# Sheet1.net
KiCad netlist of a schematic drawn in Altium Designer
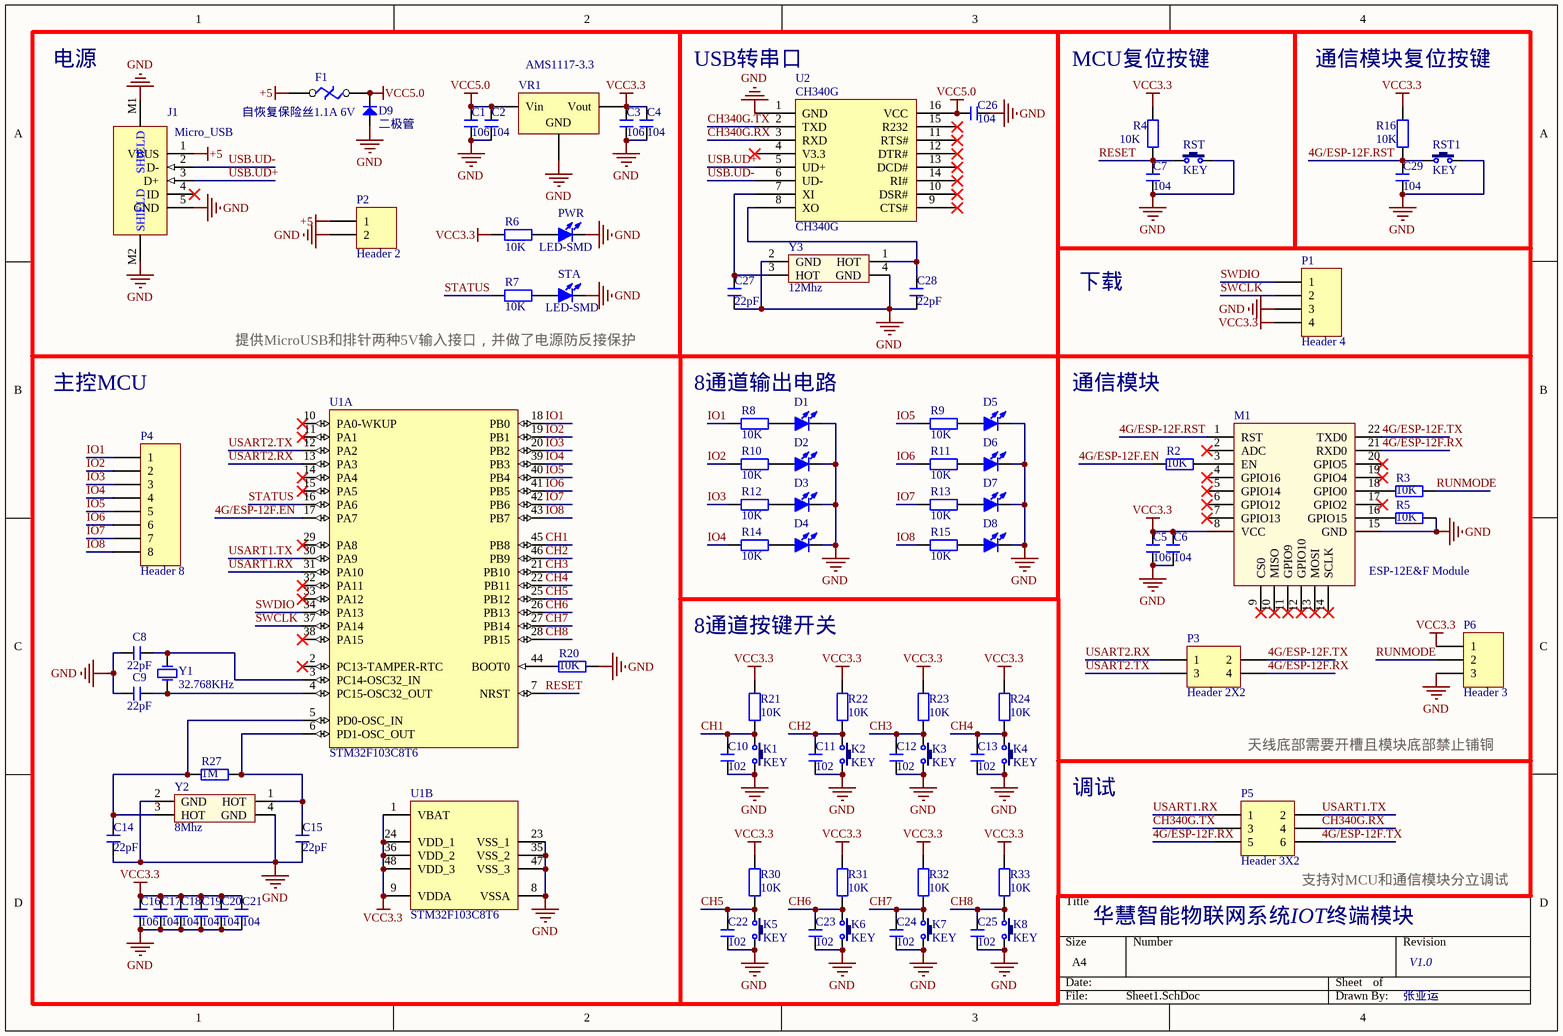
[diagram p0: Sheet1.SchDoc]

(export (version "E")
  (design (tool "Eeschema 10.0.6"))
  (components
    (comp (ref "C1")
      (value "106")
      (footprint "LC-0603_C")
      (description "无极性贴片电容")
      (fields (field (name "版权归属") "源创客"))
      (libsource (lib "MySchlib") (part "C"))
    )
    (comp (ref "C2")
      (value "104")
      (footprint "LC-0603_C")
      (description "无极性贴片电容")
      (fields (field (name "版权归属") "源创客"))
      (libsource (lib "MySchlib") (part "C"))
    )
    (comp (ref "C3")
      (value "106")
      (footprint "LC-0603_C")
      (description "无极性贴片电容")
      (fields (field (name "版权归属") "源创客"))
      (libsource (lib "MySchlib") (part "C"))
    )
    (comp (ref "C4")
      (value "104")
      (footprint "LC-0603_C")
      (description "无极性贴片电容")
      (fields (field (name "版权归属") "源创客"))
      (libsource (lib "MySchlib") (part "C"))
    )
    (comp (ref "C5")
      (value "106")
      (footprint "LC-0603_C")
      (description "无极性贴片电容")
      (fields (field (name "版权归属") "源创客"))
      (libsource (lib "MySchlib") (part "C"))
    )
    (comp (ref "C6")
      (value "104")
      (footprint "LC-0603_C")
      (description "无极性贴片电容")
      (fields (field (name "版权归属") "源创客"))
      (libsource (lib "MySchlib") (part "C"))
    )
    (comp (ref "C7")
      (value "104")
      (footprint "LC-0603_C")
      (description "无极性贴片电容")
      (fields (field (name "版权归属") "源创客"))
      (libsource (lib "MySchlib") (part "C"))
    )
    (comp (ref "C8")
      (value "22pF")
      (footprint "LC-0603_C")
      (description "无极性贴片电容")
      (fields (field (name "版权归属") "源创客"))
      (libsource (lib "MySchlib") (part "C"))
    )
    (comp (ref "C9")
      (value "22pF")
      (footprint "LC-0603_C")
      (description "无极性贴片电容")
      (fields (field (name "版权归属") "源创客"))
      (libsource (lib "MySchlib") (part "C"))
    )
    (comp (ref "C10")
      (value "102")
      (footprint "LC-0603_C")
      (description "无极性贴片电容")
      (fields (field (name "版权归属") "源创客"))
      (libsource (lib "MySchlib") (part "C"))
    )
    (comp (ref "C11")
      (value "102")
      (footprint "LC-0603_C")
      (description "无极性贴片电容")
      (fields (field (name "版权归属") "源创客"))
      (libsource (lib "MySchlib") (part "C"))
    )
    (comp (ref "C12")
      (value "102")
      (footprint "LC-0603_C")
      (description "无极性贴片电容")
      (fields (field (name "版权归属") "源创客"))
      (libsource (lib "MySchlib") (part "C"))
    )
    (comp (ref "C13")
      (value "102")
      (footprint "LC-0603_C")
      (description "无极性贴片电容")
      (fields (field (name "版权归属") "源创客"))
      (libsource (lib "MySchlib") (part "C"))
    )
    (comp (ref "C14")
      (value "22pF")
      (footprint "LC-0603_C")
      (description "无极性贴片电容")
      (fields (field (name "版权归属") "源创客"))
      (libsource (lib "MySchlib") (part "C"))
    )
    (comp (ref "C15")
      (value "22pF")
      (footprint "LC-0603_C")
      (description "无极性贴片电容")
      (fields (field (name "版权归属") "源创客"))
      (libsource (lib "MySchlib") (part "C"))
    )
    (comp (ref "C16")
      (value "106")
      (footprint "LC-0603_C")
      (description "无极性贴片电容")
      (fields (field (name "版权归属") "源创客"))
      (libsource (lib "MySchlib") (part "C"))
    )
    (comp (ref "C17")
      (value "104")
      (footprint "LC-0603_C")
      (description "无极性贴片电容")
      (fields (field (name "版权归属") "源创客"))
      (libsource (lib "MySchlib") (part "C"))
    )
    (comp (ref "C18")
      (value "104")
      (footprint "LC-0603_C")
      (description "无极性贴片电容")
      (fields (field (name "版权归属") "源创客"))
      (libsource (lib "MySchlib") (part "C"))
    )
    (comp (ref "C19")
      (value "104")
      (footprint "LC-0603_C")
      (description "无极性贴片电容")
      (fields (field (name "版权归属") "源创客"))
      (libsource (lib "MySchlib") (part "C"))
    )
    (comp (ref "C20")
      (value "104")
      (footprint "LC-0603_C")
      (description "无极性贴片电容")
      (fields (field (name "版权归属") "源创客"))
      (libsource (lib "MySchlib") (part "C"))
    )
    (comp (ref "C21")
      (value "104")
      (footprint "LC-0603_C")
      (description "无极性贴片电容")
      (fields (field (name "版权归属") "源创客"))
      (libsource (lib "MySchlib") (part "C"))
    )
    (comp (ref "C22")
      (value "102")
      (footprint "LC-0603_C")
      (description "无极性贴片电容")
      (fields (field (name "版权归属") "源创客"))
      (libsource (lib "MySchlib") (part "C"))
    )
    (comp (ref "C23")
      (value "102")
      (footprint "LC-0603_C")
      (description "无极性贴片电容")
      (fields (field (name "版权归属") "源创客"))
      (libsource (lib "MySchlib") (part "C"))
    )
    (comp (ref "C24")
      (value "102")
      (footprint "LC-0603_C")
      (description "无极性贴片电容")
      (fields (field (name "版权归属") "源创客"))
      (libsource (lib "MySchlib") (part "C"))
    )
    (comp (ref "C25")
      (value "102")
      (footprint "LC-0603_C")
      (description "无极性贴片电容")
      (fields (field (name "版权归属") "源创客"))
      (libsource (lib "MySchlib") (part "C"))
    )
    (comp (ref "C26")
      (value "104")
      (footprint "LC-0603_C")
      (description "无极性贴片电容")
      (fields (field (name "版权归属") "源创客"))
      (libsource (lib "MySchlib") (part "C"))
    )
    (comp (ref "C27")
      (value "22pF")
      (footprint "LC-0603_C")
      (description "无极性贴片电容")
      (fields (field (name "版权归属") "源创客"))
      (libsource (lib "MySchlib") (part "C"))
    )
    (comp (ref "C28")
      (value "22pF")
      (footprint "LC-0603_C")
      (description "无极性贴片电容")
      (fields (field (name "版权归属") "源创客"))
      (libsource (lib "MySchlib") (part "C"))
    )
    (comp (ref "C29")
      (value "104")
      (footprint "LC-0603_C")
      (description "无极性贴片电容")
      (fields (field (name "版权归属") "源创客"))
      (libsource (lib "MySchlib") (part "C"))
    )
    (comp (ref "D1")
      (value "LED-SMD")
      (footprint "LC-0603_LED_S1")
      (description "贴片LED")
      (fields (field (name "版权归属") "源创客"))
      (libsource (lib "MySchlib") (part "LED-SMD"))
    )
    (comp (ref "D2")
      (value "LED-SMD")
      (footprint "LC-0603_LED_S1")
      (description "贴片LED")
      (fields (field (name "版权归属") "源创客"))
      (libsource (lib "MySchlib") (part "LED-SMD"))
    )
    (comp (ref "D3")
      (value "LED-SMD")
      (footprint "LC-0603_LED_S1")
      (description "贴片LED")
      (fields (field (name "版权归属") "源创客"))
      (libsource (lib "MySchlib") (part "LED-SMD"))
    )
    (comp (ref "D4")
      (value "LED-SMD")
      (footprint "LC-0603_LED_S1")
      (description "贴片LED")
      (fields (field (name "版权归属") "源创客"))
      (libsource (lib "MySchlib") (part "LED-SMD"))
    )
    (comp (ref "D5")
      (value "LED-SMD")
      (footprint "LC-0603_LED_S1")
      (description "贴片LED")
      (fields (field (name "版权归属") "源创客"))
      (libsource (lib "MySchlib") (part "LED-SMD"))
    )
    (comp (ref "D6")
      (value "LED-SMD")
      (footprint "LC-0603_LED_S1")
      (description "贴片LED")
      (fields (field (name "版权归属") "源创客"))
      (libsource (lib "MySchlib") (part "LED-SMD"))
    )
    (comp (ref "D7")
      (value "LED-SMD")
      (footprint "LC-0603_LED_S1")
      (description "贴片LED")
      (fields (field (name "版权归属") "源创客"))
      (libsource (lib "MySchlib") (part "LED-SMD"))
    )
    (comp (ref "D8")
      (value "LED-SMD")
      (footprint "LC-0603_LED_S1")
      (description "贴片LED")
      (fields (field (name "版权归属") "源创客"))
      (libsource (lib "MySchlib") (part "LED-SMD"))
    )
    (comp (ref "D9")
      (value "二极管")
      (footprint "LC-SOD-323")
      (description "普通二极管")
      (libsource (lib "MySchlib") (part "二极管"))
    )
    (comp (ref "F1")
      (value "自恢复保险丝1.1A 6V")
      (footprint "LC-1206_R")
      (description "1206 贴片自恢复保险丝/保险管 PPTC MF-NSMF110-2 1.1A 6V")
      (libsource (lib "MySchlib") (part "F"))
    )
    (comp (ref "J1")
      (value "Micro_USB")
      (footprint "USB-MICRO_B")
      (description "Micro_usb")
      (libsource (lib "MySchlib") (part "Micro_USB"))
    )
    (comp (ref "K1")
      (value "KEY")
      (footprint "SWT3*4")
      (description "按键")
      (fields (field (name "版权归属") "源创客"))
      (libsource (lib "MySchlib") (part "KEY"))
    )
    (comp (ref "K2")
      (value "KEY")
      (footprint "SWT3*4")
      (description "按键")
      (fields (field (name "版权归属") "源创客"))
      (libsource (lib "MySchlib") (part "KEY"))
    )
    (comp (ref "K3")
      (value "KEY")
      (footprint "SWT3*4")
      (description "按键")
      (fields (field (name "版权归属") "源创客"))
      (libsource (lib "MySchlib") (part "KEY"))
    )
    (comp (ref "K4")
      (value "KEY")
      (footprint "SWT3*4")
      (description "按键")
      (fields (field (name "版权归属") "源创客"))
      (libsource (lib "MySchlib") (part "KEY"))
    )
    (comp (ref "K5")
      (value "KEY")
      (footprint "SWT3*4")
      (description "按键")
      (fields (field (name "版权归属") "源创客"))
      (libsource (lib "MySchlib") (part "KEY"))
    )
    (comp (ref "K6")
      (value "KEY")
      (footprint "SWT3*4")
      (description "按键")
      (fields (field (name "版权归属") "源创客"))
      (libsource (lib "MySchlib") (part "KEY"))
    )
    (comp (ref "K7")
      (value "KEY")
      (footprint "SWT3*4")
      (description "按键")
      (fields (field (name "版权归属") "源创客"))
      (libsource (lib "MySchlib") (part "KEY"))
    )
    (comp (ref "K8")
      (value "KEY")
      (footprint "SWT3*4")
      (description "按键")
      (fields (field (name "版权归属") "源创客"))
      (libsource (lib "MySchlib") (part "KEY"))
    )
    (comp (ref "M1")
      (value "ESP-12E&F Module")
      (footprint "ESP-12E&F Module")
      (libsource (lib "MySchlib") (part "ESP-12E&F Module"))
    )
    (comp (ref "P1")
      (value "Header 4")
      (footprint "HDR1X4")
      (description "Header, 4-Pin")
      (fields (field (name "PUBLISHER") "Altium Limited"))
      (libsource (lib "Miscellaneous Connectors") (part "Header 4"))
    )
    (comp (ref "P2")
      (value "Header 2")
      (footprint "HDR1X2")
      (description "Header, 2-Pin")
      (fields (field (name "PUBLISHER") "Altium Limited"))
      (libsource (lib "Miscellaneous Connectors") (part "Header 2"))
    )
    (comp (ref "P3")
      (value "Header 2X2")
      (footprint "HDR2X2")
      (description "Header, 2-Pin, Dual row")
      (fields (field (name "PUBLISHER") "Altium Limited"))
      (libsource (lib "Miscellaneous Connectors") (part "Header 2X2"))
    )
    (comp (ref "P4")
      (value "Header 8")
      (footprint "HDR1X8")
      (description "Header, 8-Pin")
      (fields (field (name "PUBLISHER") "Altium Limited"))
      (libsource (lib "Miscellaneous Connectors") (part "Header 8"))
    )
    (comp (ref "P5")
      (value "Header 3X2")
      (footprint "HDR2X3")
      (description "Header, 3-Pin, Dual row")
      (fields (field (name "PUBLISHER") "Altium Limited"))
      (libsource (lib "Miscellaneous Connectors") (part "Header 3X2"))
    )
    (comp (ref "P6")
      (value "Header 3")
      (footprint "HDR1X3")
      (description "Header, 3-Pin")
      (fields (field (name "PUBLISHER") "Altium Limited"))
      (libsource (lib "Miscellaneous Connectors") (part "Header 3"))
    )
    (comp (ref "PWR")
      (value "LED-SMD")
      (footprint "LC-0603_LED_S1")
      (description "贴片LED")
      (fields (field (name "版权归属") "源创客"))
      (libsource (lib "MySchlib") (part "LED-SMD"))
    )
    (comp (ref "R2")
      (value "10K")
      (footprint "LC-0603_R")
      (description "电阻")
      (libsource (lib "") (part "R_2"))
    )
    (comp (ref "R3")
      (value "10K")
      (footprint "LC-0603_R")
      (description "电阻")
      (libsource (lib "") (part "R_2"))
    )
    (comp (ref "R4")
      (value "10K")
      (footprint "LC-0603_R")
      (description "电阻")
      (libsource (lib "MySchlib") (part "R"))
    )
    (comp (ref "R5")
      (value "10K")
      (footprint "LC-0603_R")
      (description "电阻")
      (libsource (lib "") (part "R_2"))
    )
    (comp (ref "R6")
      (value "10K")
      (footprint "LC-0603_R")
      (description "电阻")
      (libsource (lib "") (part "R_3"))
    )
    (comp (ref "R7")
      (value "10K")
      (footprint "LC-0603_R")
      (description "电阻")
      (libsource (lib "") (part "R_3"))
    )
    (comp (ref "R8")
      (value "10K")
      (footprint "LC-0603_R")
      (description "电阻")
      (libsource (lib "") (part "R_3"))
    )
    (comp (ref "R9")
      (value "10K")
      (footprint "LC-0603_R")
      (description "电阻")
      (libsource (lib "") (part "R_3"))
    )
    (comp (ref "R10")
      (value "10K")
      (footprint "LC-0603_R")
      (description "电阻")
      (libsource (lib "") (part "R_3"))
    )
    (comp (ref "R11")
      (value "10K")
      (footprint "LC-0603_R")
      (description "电阻")
      (libsource (lib "") (part "R_3"))
    )
    (comp (ref "R12")
      (value "10K")
      (footprint "LC-0603_R")
      (description "电阻")
      (libsource (lib "") (part "R_3"))
    )
    (comp (ref "R13")
      (value "10K")
      (footprint "LC-0603_R")
      (description "电阻")
      (libsource (lib "") (part "R_3"))
    )
    (comp (ref "R14")
      (value "10K")
      (footprint "LC-0603_R")
      (description "电阻")
      (libsource (lib "") (part "R_3"))
    )
    (comp (ref "R15")
      (value "10K")
      (footprint "LC-0603_R")
      (description "电阻")
      (libsource (lib "") (part "R_3"))
    )
    (comp (ref "R16")
      (value "10K")
      (footprint "LC-0603_R")
      (description "电阻")
      (libsource (lib "MySchlib") (part "R"))
    )
    (comp (ref "R20")
      (value "10K")
      (footprint "LC-0603_R")
      (description "电阻")
      (libsource (lib "") (part "R_2"))
    )
    (comp (ref "R21")
      (value "10K")
      (footprint "LC-0603_R")
      (description "电阻")
      (libsource (lib "") (part "R_1"))
    )
    (comp (ref "R22")
      (value "10K")
      (footprint "LC-0603_R")
      (description "电阻")
      (libsource (lib "") (part "R_1"))
    )
    (comp (ref "R23")
      (value "10K")
      (footprint "LC-0603_R")
      (description "电阻")
      (libsource (lib "") (part "R_1"))
    )
    (comp (ref "R24")
      (value "10K")
      (footprint "LC-0603_R")
      (description "电阻")
      (libsource (lib "") (part "R_1"))
    )
    (comp (ref "R27")
      (value "1M")
      (footprint "LC-0603_R")
      (description "电阻")
      (libsource (lib "") (part "R_2"))
    )
    (comp (ref "R30")
      (value "10K")
      (footprint "LC-0603_R")
      (description "电阻")
      (libsource (lib "") (part "R_1"))
    )
    (comp (ref "R31")
      (value "10K")
      (footprint "LC-0603_R")
      (description "电阻")
      (libsource (lib "") (part "R_1"))
    )
    (comp (ref "R32")
      (value "10K")
      (footprint "LC-0603_R")
      (description "电阻")
      (libsource (lib "") (part "R_1"))
    )
    (comp (ref "R33")
      (value "10K")
      (footprint "LC-0603_R")
      (description "电阻")
      (libsource (lib "") (part "R_1"))
    )
    (comp (ref "RST")
      (value "KEY")
      (footprint "SWT3*4")
      (description "按键")
      (fields (field (name "版权归属") "源创客"))
      (libsource (lib "") (part "KEY_1"))
    )
    (comp (ref "RST1")
      (value "KEY")
      (footprint "SWT3*4")
      (description "按键")
      (fields (field (name "版权归属") "源创客"))
      (libsource (lib "") (part "KEY_1"))
    )
    (comp (ref "STA")
      (value "LED-SMD")
      (footprint "LC-0603_LED_S1")
      (description "贴片LED")
      (fields (field (name "版权归属") "源创客"))
      (libsource (lib "MySchlib") (part "LED-SMD"))
    )
    (comp (ref "U1")
      (value "STM32F103C8T6")
      (footprint "STM-LQFP48_L")
      (libsource (lib "STMicroelectronics STM32 F1") (part "STM32F103C8T6"))
    )
    (comp (ref "U2")
      (value "CH340G")
      (footprint "SOIC-16_150mil")
      (description "USB")
      (libsource (lib "02 Miscellaneous_Devices_ZSF_Library") (part "CH340G"))
    )
    (comp (ref "VR1")
      (value "AMS1117-3.3")
      (footprint "LC-SOT-223")
      (description "低压差线性稳压(LDO)")
      (libsource (lib "MySchlib") (part "SOT-223 AMS1117-3.3"))
    )
    (comp (ref "Y1")
      (value "32.768KHz")
      (footprint "LC-SMD-3215_2P FC - 135")
      (description "普通晶振")
      (fields (field (name "PUBLISHER") "Altium Limited"))
      (libsource (lib "MySchlib") (part "XTAL"))
    )
    (comp (ref "Y2")
      (value "8Mhz")
      (footprint "LC-SMD-3225_4P")
      (description "3225贴片无源晶振")
      (libsource (lib "MySchlib") (part "XTAL_3225"))
    )
    (comp (ref "Y3")
      (value "12Mhz")
      (footprint "LC-SMD-3225_4P")
      (description "3225贴片无源晶振")
      (libsource (lib "MySchlib") (part "XTAL_3225"))
    )
  )
  (nets
    (net (code "1") (name "+5") (class "Default")
      (node (ref "F1") (pin "1") (pinfunction "1_1") (pintype "passive"))
      (node (ref "J1") (pin "1") (pinfunction "VBUS_1") (pintype "power_in"))
      (node (ref "P2") (pin "1") (pinfunction "1_1") (pintype "passive"))
    )
    (net (code "2") (name "/4G{slash}ESP-12F.EN") (class "Default")
      (node (ref "R2") (pin "2") (pinfunction "2_2") (pintype "passive"))
      (node (ref "U1") (pin "17") (pinfunction "PA7_17") (pintype "bidirectional"))
    )
    (net (code "3") (name "/4G{slash}ESP-12F.RST") (class "Default")
      (node (ref "C29") (pin "2") (pinfunction "2_2") (pintype "passive"))
      (node (ref "M1") (pin "1") (pinfunction "RST_1") (pintype "passive"))
      (node (ref "R16") (pin "1") (pinfunction "1_1") (pintype "passive"))
      (node (ref "RST1") (pin "1") (pinfunction "1_1") (pintype "passive"))
    )
    (net (code "4") (name "/4G{slash}ESP-12F.RX") (class "Default")
      (node (ref "M1") (pin "21") (pinfunction "RXD0_21") (pintype "passive"))
      (node (ref "P3") (pin "4") (pinfunction "4_4") (pintype "passive"))
      (node (ref "P5") (pin "5") (pinfunction "5_5") (pintype "passive"))
    )
    (net (code "5") (name "/4G{slash}ESP-12F.TX") (class "Default")
      (node (ref "M1") (pin "22") (pinfunction "TXD0_22") (pintype "passive"))
      (node (ref "P3") (pin "2") (pinfunction "2_2") (pintype "passive"))
      (node (ref "P5") (pin "6") (pinfunction "6_6") (pintype "passive"))
    )
    (net (code "6") (name "/CH1") (class "Default")
      (node (ref "C10") (pin "1") (pinfunction "1_1") (pintype "passive"))
      (node (ref "K1") (pin "1") (pinfunction "1_1") (pintype "passive"))
      (node (ref "R21") (pin "2") (pinfunction "2_2") (pintype "passive"))
      (node (ref "U1") (pin "45") (pinfunction "PB8_45") (pintype "bidirectional"))
    )
    (net (code "7") (name "/CH2") (class "Default")
      (node (ref "C11") (pin "1") (pinfunction "1_1") (pintype "passive"))
      (node (ref "K2") (pin "1") (pinfunction "1_1") (pintype "passive"))
      (node (ref "R22") (pin "2") (pinfunction "2_2") (pintype "passive"))
      (node (ref "U1") (pin "46") (pinfunction "PB9_46") (pintype "bidirectional"))
    )
    (net (code "8") (name "/CH3") (class "Default")
      (node (ref "C12") (pin "1") (pinfunction "1_1") (pintype "passive"))
      (node (ref "K3") (pin "1") (pinfunction "1_1") (pintype "passive"))
      (node (ref "R23") (pin "2") (pinfunction "2_2") (pintype "passive"))
      (node (ref "U1") (pin "21") (pinfunction "PB10_21") (pintype "bidirectional"))
    )
    (net (code "9") (name "/CH4") (class "Default")
      (node (ref "C13") (pin "1") (pinfunction "1_1") (pintype "passive"))
      (node (ref "K4") (pin "1") (pinfunction "1_1") (pintype "passive"))
      (node (ref "R24") (pin "2") (pinfunction "2_2") (pintype "passive"))
      (node (ref "U1") (pin "22") (pinfunction "PB11_22") (pintype "bidirectional"))
    )
    (net (code "10") (name "/CH5") (class "Default")
      (node (ref "C22") (pin "1") (pinfunction "1_1") (pintype "passive"))
      (node (ref "K5") (pin "1") (pinfunction "1_1") (pintype "passive"))
      (node (ref "R30") (pin "2") (pinfunction "2_2") (pintype "passive"))
      (node (ref "U1") (pin "25") (pinfunction "PB12_25") (pintype "bidirectional"))
    )
    (net (code "11") (name "/CH6") (class "Default")
      (node (ref "C23") (pin "1") (pinfunction "1_1") (pintype "passive"))
      (node (ref "K6") (pin "1") (pinfunction "1_1") (pintype "passive"))
      (node (ref "R31") (pin "2") (pinfunction "2_2") (pintype "passive"))
      (node (ref "U1") (pin "26") (pinfunction "PB13_26") (pintype "bidirectional"))
    )
    (net (code "12") (name "/CH7") (class "Default")
      (node (ref "C24") (pin "1") (pinfunction "1_1") (pintype "passive"))
      (node (ref "K7") (pin "1") (pinfunction "1_1") (pintype "passive"))
      (node (ref "R32") (pin "2") (pinfunction "2_2") (pintype "passive"))
      (node (ref "U1") (pin "27") (pinfunction "PB14_27") (pintype "bidirectional"))
    )
    (net (code "13") (name "/CH8") (class "Default")
      (node (ref "C25") (pin "1") (pinfunction "1_1") (pintype "passive"))
      (node (ref "K8") (pin "1") (pinfunction "1_1") (pintype "passive"))
      (node (ref "R33") (pin "2") (pinfunction "2_2") (pintype "passive"))
      (node (ref "U1") (pin "28") (pinfunction "PB15_28") (pintype "bidirectional"))
    )
    (net (code "14") (name "/CH340G.RX") (class "Default")
      (node (ref "P5") (pin "4") (pinfunction "4_4") (pintype "passive"))
      (node (ref "U2") (pin "3") (pinfunction "RXD_3") (pintype "passive"))
    )
    (net (code "15") (name "/CH340G.TX") (class "Default")
      (node (ref "P5") (pin "3") (pinfunction "3_3") (pintype "passive"))
      (node (ref "U2") (pin "2") (pinfunction "TXD_2") (pintype "passive"))
    )
    (net (code "16") (name "/IO1") (class "Default")
      (node (ref "P4") (pin "1") (pinfunction "1_1") (pintype "passive"))
      (node (ref "R8") (pin "1") (pinfunction "1_1") (pintype "passive"))
      (node (ref "U1") (pin "18") (pinfunction "PB0_18") (pintype "bidirectional"))
    )
    (net (code "17") (name "/IO2") (class "Default")
      (node (ref "P4") (pin "2") (pinfunction "2_2") (pintype "passive"))
      (node (ref "R10") (pin "1") (pinfunction "1_1") (pintype "passive"))
      (node (ref "U1") (pin "19") (pinfunction "PB1_19") (pintype "bidirectional"))
    )
    (net (code "18") (name "/IO3") (class "Default")
      (node (ref "P4") (pin "3") (pinfunction "3_3") (pintype "passive"))
      (node (ref "R12") (pin "1") (pinfunction "1_1") (pintype "passive"))
      (node (ref "U1") (pin "20") (pinfunction "PB2_20") (pintype "bidirectional"))
    )
    (net (code "19") (name "/IO4") (class "Default")
      (node (ref "P4") (pin "4") (pinfunction "4_4") (pintype "passive"))
      (node (ref "R14") (pin "1") (pinfunction "1_1") (pintype "passive"))
      (node (ref "U1") (pin "39") (pinfunction "PB3_39") (pintype "bidirectional"))
    )
    (net (code "20") (name "/IO5") (class "Default")
      (node (ref "P4") (pin "5") (pinfunction "5_5") (pintype "passive"))
      (node (ref "R9") (pin "1") (pinfunction "1_1") (pintype "passive"))
      (node (ref "U1") (pin "40") (pinfunction "PB4_40") (pintype "bidirectional"))
    )
    (net (code "21") (name "/IO6") (class "Default")
      (node (ref "P4") (pin "6") (pinfunction "6_6") (pintype "passive"))
      (node (ref "R11") (pin "1") (pinfunction "1_1") (pintype "passive"))
      (node (ref "U1") (pin "41") (pinfunction "PB5_41") (pintype "bidirectional"))
    )
    (net (code "22") (name "/IO7") (class "Default")
      (node (ref "P4") (pin "7") (pinfunction "7_7") (pintype "passive"))
      (node (ref "R13") (pin "1") (pinfunction "1_1") (pintype "passive"))
      (node (ref "U1") (pin "42") (pinfunction "PB6_42") (pintype "bidirectional"))
    )
    (net (code "23") (name "/IO8") (class "Default")
      (node (ref "P4") (pin "8") (pinfunction "8_8") (pintype "passive"))
      (node (ref "R15") (pin "1") (pinfunction "1_1") (pintype "passive"))
      (node (ref "U1") (pin "43") (pinfunction "PB7_43") (pintype "bidirectional"))
    )
    (net (code "24") (name "/RESET") (class "Default")
      (node (ref "C7") (pin "2") (pinfunction "2_2") (pintype "passive"))
      (node (ref "R4") (pin "1") (pinfunction "1_1") (pintype "passive"))
      (node (ref "RST") (pin "1") (pinfunction "1_1") (pintype "passive"))
      (node (ref "U1") (pin "7") (pinfunction "NRST_7") (pintype "bidirectional"))
    )
    (net (code "25") (name "/RUNMODE") (class "Default")
      (node (ref "P6") (pin "2") (pinfunction "2_2") (pintype "passive"))
      (node (ref "R3") (pin "1") (pinfunction "1_1") (pintype "passive"))
    )
    (net (code "26") (name "/STATUS") (class "Default")
      (node (ref "R7") (pin "1") (pinfunction "1_1") (pintype "passive"))
      (node (ref "U1") (pin "16") (pinfunction "PA6_16") (pintype "bidirectional"))
    )
    (net (code "27") (name "/SWCLK") (class "Default")
      (node (ref "P1") (pin "2") (pinfunction "2_2") (pintype "passive"))
      (node (ref "U1") (pin "37") (pinfunction "PA14_37") (pintype "bidirectional"))
    )
    (net (code "28") (name "/SWDIO") (class "Default")
      (node (ref "P1") (pin "1") (pinfunction "1_1") (pintype "passive"))
      (node (ref "U1") (pin "34") (pinfunction "PA13_34") (pintype "bidirectional"))
    )
    (net (code "29") (name "/USART1.RX") (class "Default")
      (node (ref "P5") (pin "1") (pinfunction "1_1") (pintype "passive"))
      (node (ref "U1") (pin "31") (pinfunction "PA10_31") (pintype "bidirectional"))
    )
    (net (code "30") (name "/USART1.TX") (class "Default")
      (node (ref "P5") (pin "2") (pinfunction "2_2") (pintype "passive"))
      (node (ref "U1") (pin "30") (pinfunction "PA9_30") (pintype "bidirectional"))
    )
    (net (code "31") (name "/USART2.RX") (class "Default")
      (node (ref "P3") (pin "1") (pinfunction "1_1") (pintype "passive"))
      (node (ref "U1") (pin "13") (pinfunction "PA3_13") (pintype "bidirectional"))
    )
    (net (code "32") (name "/USART2.TX") (class "Default")
      (node (ref "P3") (pin "3") (pinfunction "3_3") (pintype "passive"))
      (node (ref "U1") (pin "12") (pinfunction "PA2_12") (pintype "bidirectional"))
    )
    (net (code "33") (name "/USB.UD+") (class "Default")
      (node (ref "J1") (pin "3") (pinfunction "D+_3") (pintype "input"))
      (node (ref "U2") (pin "5") (pinfunction "UD+_5") (pintype "passive"))
    )
    (net (code "34") (name "/USB.UD-") (class "Default")
      (node (ref "J1") (pin "2") (pinfunction "D-_2") (pintype "input"))
      (node (ref "U2") (pin "6") (pinfunction "UD-_6") (pintype "passive"))
    )
    (net (code "35") (name "GND") (class "Default")
      (node (ref "C1") (pin "2") (pinfunction "2_2") (pintype "passive"))
      (node (ref "C10") (pin "2") (pinfunction "2_2") (pintype "passive"))
      (node (ref "C11") (pin "2") (pinfunction "2_2") (pintype "passive"))
      (node (ref "C12") (pin "2") (pinfunction "2_2") (pintype "passive"))
      (node (ref "C13") (pin "2") (pinfunction "2_2") (pintype "passive"))
      (node (ref "C14") (pin "2") (pinfunction "2_2") (pintype "passive"))
      (node (ref "C15") (pin "2") (pinfunction "2_2") (pintype "passive"))
      (node (ref "C16") (pin "2") (pinfunction "2_2") (pintype "passive"))
      (node (ref "C17") (pin "2") (pinfunction "2_2") (pintype "passive"))
      (node (ref "C18") (pin "2") (pinfunction "2_2") (pintype "passive"))
      (node (ref "C19") (pin "2") (pinfunction "2_2") (pintype "passive"))
      (node (ref "C2") (pin "2") (pinfunction "2_2") (pintype "passive"))
      (node (ref "C20") (pin "2") (pinfunction "2_2") (pintype "passive"))
      (node (ref "C21") (pin "2") (pinfunction "2_2") (pintype "passive"))
      (node (ref "C22") (pin "2") (pinfunction "2_2") (pintype "passive"))
      (node (ref "C23") (pin "2") (pinfunction "2_2") (pintype "passive"))
      (node (ref "C24") (pin "2") (pinfunction "2_2") (pintype "passive"))
      (node (ref "C25") (pin "2") (pinfunction "2_2") (pintype "passive"))
      (node (ref "C26") (pin "1") (pinfunction "1_1") (pintype "passive"))
      (node (ref "C27") (pin "2") (pinfunction "2_2") (pintype "passive"))
      (node (ref "C28") (pin "2") (pinfunction "2_2") (pintype "passive"))
      (node (ref "C29") (pin "1") (pinfunction "1_1") (pintype "passive"))
      (node (ref "C3") (pin "2") (pinfunction "2_2") (pintype "passive"))
      (node (ref "C4") (pin "2") (pinfunction "2_2") (pintype "passive"))
      (node (ref "C5") (pin "2") (pinfunction "2_2") (pintype "passive"))
      (node (ref "C6") (pin "2") (pinfunction "2_2") (pintype "passive"))
      (node (ref "C7") (pin "1") (pinfunction "1_1") (pintype "passive"))
      (node (ref "C8") (pin "1") (pinfunction "1_1") (pintype "passive"))
      (node (ref "C9") (pin "1") (pinfunction "1_1") (pintype "passive"))
      (node (ref "D1") (pin "2") (pinfunction "K_2") (pintype "passive"))
      (node (ref "D2") (pin "2") (pinfunction "K_2") (pintype "passive"))
      (node (ref "D3") (pin "2") (pinfunction "K_2") (pintype "passive"))
      (node (ref "D4") (pin "2") (pinfunction "K_2") (pintype "passive"))
      (node (ref "D5") (pin "2") (pinfunction "K_2") (pintype "passive"))
      (node (ref "D6") (pin "2") (pinfunction "K_2") (pintype "passive"))
      (node (ref "D7") (pin "2") (pinfunction "K_2") (pintype "passive"))
      (node (ref "D8") (pin "2") (pinfunction "K_2") (pintype "passive"))
      (node (ref "D9") (pin "1") (pintype "passive"))
      (node (ref "J1") (pin "5") (pinfunction "GND_5") (pintype "power_in"))
      (node (ref "J1") (pin "M1") (pinfunction "SHIELD_M1") (pintype "passive"))
      (node (ref "J1") (pin "M2") (pinfunction "SHIELD_M2") (pintype "passive"))
      (node (ref "K1") (pin "2") (pinfunction "2_2") (pintype "passive"))
      (node (ref "K2") (pin "2") (pinfunction "2_2") (pintype "passive"))
      (node (ref "K3") (pin "2") (pinfunction "2_2") (pintype "passive"))
      (node (ref "K4") (pin "2") (pinfunction "2_2") (pintype "passive"))
      (node (ref "K5") (pin "2") (pinfunction "2_2") (pintype "passive"))
      (node (ref "K6") (pin "2") (pinfunction "2_2") (pintype "passive"))
      (node (ref "K7") (pin "2") (pinfunction "2_2") (pintype "passive"))
      (node (ref "K8") (pin "2") (pinfunction "2_2") (pintype "passive"))
      (node (ref "M1") (pin "15") (pinfunction "GND_15") (pintype "passive"))
      (node (ref "P1") (pin "3") (pinfunction "3_3") (pintype "passive"))
      (node (ref "P2") (pin "2") (pinfunction "2_2") (pintype "passive"))
      (node (ref "P6") (pin "3") (pinfunction "3_3") (pintype "passive"))
      (node (ref "PWR") (pin "2") (pinfunction "K_2") (pintype "passive"))
      (node (ref "R20") (pin "1") (pinfunction "1_1") (pintype "passive"))
      (node (ref "R5") (pin "1") (pinfunction "1_1") (pintype "passive"))
      (node (ref "RST") (pin "2") (pinfunction "2_2") (pintype "passive"))
      (node (ref "RST1") (pin "2") (pinfunction "2_2") (pintype "passive"))
      (node (ref "STA") (pin "2") (pinfunction "K_2") (pintype "passive"))
      (node (ref "U1") (pin "23") (pinfunction "VSS_1_23") (pintype "power_in"))
      (node (ref "U1") (pin "35") (pinfunction "VSS_2_35") (pintype "power_in"))
      (node (ref "U1") (pin "47") (pinfunction "VSS_3_47") (pintype "power_in"))
      (node (ref "U1") (pin "8") (pinfunction "VSSA_8") (pintype "power_in"))
      (node (ref "U2") (pin "1") (pinfunction "GND_1") (pintype "passive"))
      (node (ref "VR1") (pin "1") (pinfunction "GND_1") (pintype "passive"))
      (node (ref "Y2") (pin "2") (pinfunction "GND_2") (pintype "passive"))
      (node (ref "Y2") (pin "4") (pinfunction "GND_4") (pintype "passive"))
      (node (ref "Y3") (pin "2") (pinfunction "GND_2") (pintype "passive"))
      (node (ref "Y3") (pin "4") (pinfunction "GND_4") (pintype "passive"))
    )
    (net (code "36") (name "Net-(D1-A)") (class "Default")
      (node (ref "D1") (pin "1") (pinfunction "A_1") (pintype "passive"))
      (node (ref "R8") (pin "2") (pinfunction "2_2") (pintype "passive"))
    )
    (net (code "37") (name "Net-(D2-A)") (class "Default")
      (node (ref "D2") (pin "1") (pinfunction "A_1") (pintype "passive"))
      (node (ref "R10") (pin "2") (pinfunction "2_2") (pintype "passive"))
    )
    (net (code "38") (name "Net-(D3-A)") (class "Default")
      (node (ref "D3") (pin "1") (pinfunction "A_1") (pintype "passive"))
      (node (ref "R12") (pin "2") (pinfunction "2_2") (pintype "passive"))
    )
    (net (code "39") (name "Net-(D4-A)") (class "Default")
      (node (ref "D4") (pin "1") (pinfunction "A_1") (pintype "passive"))
      (node (ref "R14") (pin "2") (pinfunction "2_2") (pintype "passive"))
    )
    (net (code "40") (name "Net-(D5-A)") (class "Default")
      (node (ref "D5") (pin "1") (pinfunction "A_1") (pintype "passive"))
      (node (ref "R9") (pin "2") (pinfunction "2_2") (pintype "passive"))
    )
    (net (code "41") (name "Net-(D6-A)") (class "Default")
      (node (ref "D6") (pin "1") (pinfunction "A_1") (pintype "passive"))
      (node (ref "R11") (pin "2") (pinfunction "2_2") (pintype "passive"))
    )
    (net (code "42") (name "Net-(D7-A)") (class "Default")
      (node (ref "D7") (pin "1") (pinfunction "A_1") (pintype "passive"))
      (node (ref "R13") (pin "2") (pinfunction "2_2") (pintype "passive"))
    )
    (net (code "43") (name "Net-(D8-A)") (class "Default")
      (node (ref "D8") (pin "1") (pinfunction "A_1") (pintype "passive"))
      (node (ref "R15") (pin "2") (pinfunction "2_2") (pintype "passive"))
    )
    (net (code "44") (name "Net-(M1-EN)") (class "Default")
      (node (ref "M1") (pin "3") (pinfunction "EN_3") (pintype "passive"))
      (node (ref "R2") (pin "1") (pinfunction "1_1") (pintype "passive"))
    )
    (net (code "45") (name "Net-(M1-GPIO0)") (class "Default")
      (node (ref "M1") (pin "18") (pinfunction "GPIO0_18") (pintype "passive"))
      (node (ref "R3") (pin "2") (pinfunction "2_2") (pintype "passive"))
    )
    (net (code "46") (name "Net-(M1-GPIO15)") (class "Default")
      (node (ref "M1") (pin "16") (pinfunction "GPIO15_16") (pintype "passive"))
      (node (ref "R5") (pin "2") (pinfunction "2_2") (pintype "passive"))
    )
    (net (code "47") (name "Net-(PWR-A)") (class "Default")
      (node (ref "PWR") (pin "1") (pinfunction "A_1") (pintype "passive"))
      (node (ref "R6") (pin "2") (pinfunction "2_2") (pintype "passive"))
    )
    (net (code "48") (name "Net-(STA-A)") (class "Default")
      (node (ref "R7") (pin "2") (pinfunction "2_2") (pintype "passive"))
      (node (ref "STA") (pin "1") (pinfunction "A_1") (pintype "passive"))
    )
    (net (code "49") (name "Net-(U1A-BOOT0)") (class "Default")
      (node (ref "R20") (pin "2") (pinfunction "2_2") (pintype "passive"))
      (node (ref "U1") (pin "44") (pinfunction "BOOT0_44") (pintype "input"))
    )
    (net (code "50") (name "Net-(U1A-PC14-OSC32_IN)") (class "Default")
      (node (ref "C8") (pin "2") (pinfunction "2_2") (pintype "passive"))
      (node (ref "U1") (pin "3") (pinfunction "PC14-OSC32_IN_3") (pintype "bidirectional"))
      (node (ref "Y1") (pin "2") (pinfunction "OSC2_2") (pintype "passive"))
    )
    (net (code "51") (name "Net-(U1A-PC15-OSC32_OUT)") (class "Default")
      (node (ref "C9") (pin "2") (pinfunction "2_2") (pintype "passive"))
      (node (ref "U1") (pin "4") (pinfunction "PC15-OSC32_OUT_4") (pintype "bidirectional"))
      (node (ref "Y1") (pin "1") (pinfunction "OSC1_1") (pintype "passive"))
    )
    (net (code "52") (name "Net-(U1A-PD0-OSC_IN)") (class "Default")
      (node (ref "C14") (pin "1") (pinfunction "1_1") (pintype "passive"))
      (node (ref "R27") (pin "2") (pinfunction "2_2") (pintype "passive"))
      (node (ref "U1") (pin "5") (pinfunction "PD0-OSC_IN_5") (pintype "bidirectional"))
      (node (ref "Y2") (pin "3") (pinfunction "HOT_3") (pintype "passive"))
    )
    (net (code "53") (name "Net-(U1A-PD1-OSC_OUT)") (class "Default")
      (node (ref "C15") (pin "1") (pinfunction "1_1") (pintype "passive"))
      (node (ref "R27") (pin "1") (pinfunction "1_1") (pintype "passive"))
      (node (ref "U1") (pin "6") (pinfunction "PD1-OSC_OUT_6") (pintype "bidirectional"))
      (node (ref "Y2") (pin "1") (pinfunction "HOT_1") (pintype "passive"))
    )
    (net (code "54") (name "Net-(U2-XI)") (class "Default")
      (node (ref "C27") (pin "1") (pinfunction "1_1") (pintype "passive"))
      (node (ref "U2") (pin "7") (pinfunction "XI_7") (pintype "passive"))
      (node (ref "Y3") (pin "3") (pinfunction "HOT_3") (pintype "passive"))
    )
    (net (code "55") (name "Net-(U2-XO)") (class "Default")
      (node (ref "C28") (pin "1") (pinfunction "1_1") (pintype "passive"))
      (node (ref "U2") (pin "8") (pinfunction "XO_8") (pintype "passive"))
      (node (ref "Y3") (pin "1") (pinfunction "HOT_1") (pintype "passive"))
    )
    (net (code "56") (name "VCC3.3") (class "Default")
      (node (ref "C16") (pin "1") (pinfunction "1_1") (pintype "passive"))
      (node (ref "C17") (pin "1") (pinfunction "1_1") (pintype "passive"))
      (node (ref "C18") (pin "1") (pinfunction "1_1") (pintype "passive"))
      (node (ref "C19") (pin "1") (pinfunction "1_1") (pintype "passive"))
      (node (ref "C20") (pin "1") (pinfunction "1_1") (pintype "passive"))
      (node (ref "C21") (pin "1") (pinfunction "1_1") (pintype "passive"))
      (node (ref "C3") (pin "1") (pinfunction "1_1") (pintype "passive"))
      (node (ref "C4") (pin "1") (pinfunction "1_1") (pintype "passive"))
      (node (ref "C5") (pin "1") (pinfunction "1_1") (pintype "passive"))
      (node (ref "C6") (pin "1") (pinfunction "1_1") (pintype "passive"))
      (node (ref "M1") (pin "8") (pinfunction "VCC_8") (pintype "passive"))
      (node (ref "P1") (pin "4") (pinfunction "4_4") (pintype "passive"))
      (node (ref "P6") (pin "1") (pinfunction "1_1") (pintype "passive"))
      (node (ref "R16") (pin "2") (pinfunction "2_2") (pintype "passive"))
      (node (ref "R21") (pin "1") (pinfunction "1_1") (pintype "passive"))
      (node (ref "R22") (pin "1") (pinfunction "1_1") (pintype "passive"))
      (node (ref "R23") (pin "1") (pinfunction "1_1") (pintype "passive"))
      (node (ref "R24") (pin "1") (pinfunction "1_1") (pintype "passive"))
      (node (ref "R30") (pin "1") (pinfunction "1_1") (pintype "passive"))
      (node (ref "R31") (pin "1") (pinfunction "1_1") (pintype "passive"))
      (node (ref "R32") (pin "1") (pinfunction "1_1") (pintype "passive"))
      (node (ref "R33") (pin "1") (pinfunction "1_1") (pintype "passive"))
      (node (ref "R4") (pin "2") (pinfunction "2_2") (pintype "passive"))
      (node (ref "R6") (pin "1") (pinfunction "1_1") (pintype "passive"))
      (node (ref "U1") (pin "1") (pinfunction "VBAT_1") (pintype "power_in"))
      (node (ref "U1") (pin "24") (pinfunction "VDD_1_24") (pintype "power_in"))
      (node (ref "U1") (pin "36") (pinfunction "VDD_2_36") (pintype "power_in"))
      (node (ref "U1") (pin "48") (pinfunction "VDD_3_48") (pintype "power_in"))
      (node (ref "U1") (pin "9") (pinfunction "VDDA_9") (pintype "power_in"))
      (node (ref "VR1") (pin "2") (pinfunction "Vout_2") (pintype "passive"))
    )
    (net (code "57") (name "VCC5.0") (class "Default")
      (node (ref "C1") (pin "1") (pinfunction "1_1") (pintype "passive"))
      (node (ref "C2") (pin "1") (pinfunction "1_1") (pintype "passive"))
      (node (ref "C26") (pin "2") (pinfunction "2_2") (pintype "passive"))
      (node (ref "D9") (pin "2") (pintype "passive"))
      (node (ref "F1") (pin "2") (pinfunction "2_2") (pintype "passive"))
      (node (ref "U2") (pin "16") (pinfunction "VCC_16") (pintype "passive"))
      (node (ref "VR1") (pin "3") (pinfunction "Vin_3") (pintype "passive"))
    )
    (net (code "58") (name "unconnected-(J1-ID-Pad4)") (class "Default")
      (node (ref "J1") (pin "4") (pinfunction "ID_4") (pintype "passive+no_connect"))
    )
    (net (code "59") (name "unconnected-(M1-ADC-Pad2)") (class "Default")
      (node (ref "M1") (pin "2") (pinfunction "ADC_2") (pintype "passive+no_connect"))
    )
    (net (code "60") (name "unconnected-(M1-CS0-Pad9)") (class "Default")
      (node (ref "M1") (pin "9") (pinfunction "CS0_9") (pintype "passive+no_connect"))
    )
    (net (code "61") (name "unconnected-(M1-GPIO2-Pad17)") (class "Default")
      (node (ref "M1") (pin "17") (pinfunction "GPIO2_17") (pintype "passive+no_connect"))
    )
    (net (code "62") (name "unconnected-(M1-GPIO4-Pad19)") (class "Default")
      (node (ref "M1") (pin "19") (pinfunction "GPIO4_19") (pintype "passive+no_connect"))
    )
    (net (code "63") (name "unconnected-(M1-GPIO5-Pad20)") (class "Default")
      (node (ref "M1") (pin "20") (pinfunction "GPIO5_20") (pintype "passive+no_connect"))
    )
    (net (code "64") (name "unconnected-(M1-GPIO9-Pad11)") (class "Default")
      (node (ref "M1") (pin "11") (pinfunction "GPIO9_11") (pintype "passive+no_connect"))
    )
    (net (code "65") (name "unconnected-(M1-GPIO10-Pad12)") (class "Default")
      (node (ref "M1") (pin "12") (pinfunction "GPIO10_12") (pintype "passive+no_connect"))
    )
    (net (code "66") (name "unconnected-(M1-GPIO12-Pad6)") (class "Default")
      (node (ref "M1") (pin "6") (pinfunction "GPIO12_6") (pintype "passive+no_connect"))
    )
    (net (code "67") (name "unconnected-(M1-GPIO13-Pad7)") (class "Default")
      (node (ref "M1") (pin "7") (pinfunction "GPIO13_7") (pintype "passive+no_connect"))
    )
    (net (code "68") (name "unconnected-(M1-GPIO14-Pad5)") (class "Default")
      (node (ref "M1") (pin "5") (pinfunction "GPIO14_5") (pintype "passive+no_connect"))
    )
    (net (code "69") (name "unconnected-(M1-GPIO16-Pad4)") (class "Default")
      (node (ref "M1") (pin "4") (pinfunction "GPIO16_4") (pintype "passive+no_connect"))
    )
    (net (code "70") (name "unconnected-(M1-MISO-Pad10)") (class "Default")
      (node (ref "M1") (pin "10") (pinfunction "MISO_10") (pintype "passive+no_connect"))
    )
    (net (code "71") (name "unconnected-(M1-MOSI-Pad13)") (class "Default")
      (node (ref "M1") (pin "13") (pinfunction "MOSI_13") (pintype "passive+no_connect"))
    )
    (net (code "72") (name "unconnected-(M1-SCLK-Pad14)") (class "Default")
      (node (ref "M1") (pin "14") (pinfunction "SCLK_14") (pintype "passive+no_connect"))
    )
    (net (code "73") (name "unconnected-(U1A-PA0-WKUP-Pad10)") (class "Default")
      (node (ref "U1") (pin "10") (pinfunction "PA0-WKUP_10") (pintype "bidirectional+no_connect"))
    )
    (net (code "74") (name "unconnected-(U1A-PA1-Pad11)") (class "Default")
      (node (ref "U1") (pin "11") (pinfunction "PA1_11") (pintype "bidirectional+no_connect"))
    )
    (net (code "75") (name "unconnected-(U1A-PA4-Pad14)") (class "Default")
      (node (ref "U1") (pin "14") (pinfunction "PA4_14") (pintype "bidirectional+no_connect"))
    )
    (net (code "76") (name "unconnected-(U1A-PA5-Pad15)") (class "Default")
      (node (ref "U1") (pin "15") (pinfunction "PA5_15") (pintype "bidirectional+no_connect"))
    )
    (net (code "77") (name "unconnected-(U1A-PA8-Pad29)") (class "Default")
      (node (ref "U1") (pin "29") (pinfunction "PA8_29") (pintype "bidirectional+no_connect"))
    )
    (net (code "78") (name "unconnected-(U1A-PA11-Pad32)") (class "Default")
      (node (ref "U1") (pin "32") (pinfunction "PA11_32") (pintype "bidirectional+no_connect"))
    )
    (net (code "79") (name "unconnected-(U1A-PA12-Pad33)") (class "Default")
      (node (ref "U1") (pin "33") (pinfunction "PA12_33") (pintype "bidirectional+no_connect"))
    )
    (net (code "80") (name "unconnected-(U1A-PA15-Pad38)") (class "Default")
      (node (ref "U1") (pin "38") (pinfunction "PA15_38") (pintype "bidirectional+no_connect"))
    )
    (net (code "81") (name "unconnected-(U1A-PC13-TAMPER-RTC-Pad2)") (class "Default")
      (node (ref "U1") (pin "2") (pinfunction "PC13-TAMPER-RTC_2") (pintype "bidirectional+no_connect"))
    )
    (net (code "82") (name "unconnected-(U2-CTS#-Pad9)") (class "Default")
      (node (ref "U2") (pin "9") (pinfunction "CTS#_9") (pintype "passive+no_connect"))
    )
    (net (code "83") (name "unconnected-(U2-DCD#-Pad13)") (class "Default")
      (node (ref "U2") (pin "13") (pinfunction "DCD#_13") (pintype "passive+no_connect"))
    )
    (net (code "84") (name "unconnected-(U2-DSR#-Pad10)") (class "Default")
      (node (ref "U2") (pin "10") (pinfunction "DSR#_10") (pintype "passive+no_connect"))
    )
    (net (code "85") (name "unconnected-(U2-DTR#-Pad12)") (class "Default")
      (node (ref "U2") (pin "12") (pinfunction "DTR#_12") (pintype "passive+no_connect"))
    )
    (net (code "86") (name "unconnected-(U2-R232-Pad15)") (class "Default")
      (node (ref "U2") (pin "15") (pinfunction "R232_15") (pintype "passive+no_connect"))
    )
    (net (code "87") (name "unconnected-(U2-RI#-Pad14)") (class "Default")
      (node (ref "U2") (pin "14") (pinfunction "RI#_14") (pintype "passive+no_connect"))
    )
    (net (code "88") (name "unconnected-(U2-RTS#-Pad11)") (class "Default")
      (node (ref "U2") (pin "11") (pinfunction "RTS#_11") (pintype "passive+no_connect"))
    )
    (net (code "89") (name "unconnected-(U2-V3.3-Pad4)") (class "Default")
      (node (ref "U2") (pin "4") (pinfunction "V3.3_4") (pintype "passive+no_connect"))
    )
  )
)
